# ZynqPower.net
KiCad netlist of a schematic drawn in Altium Designer
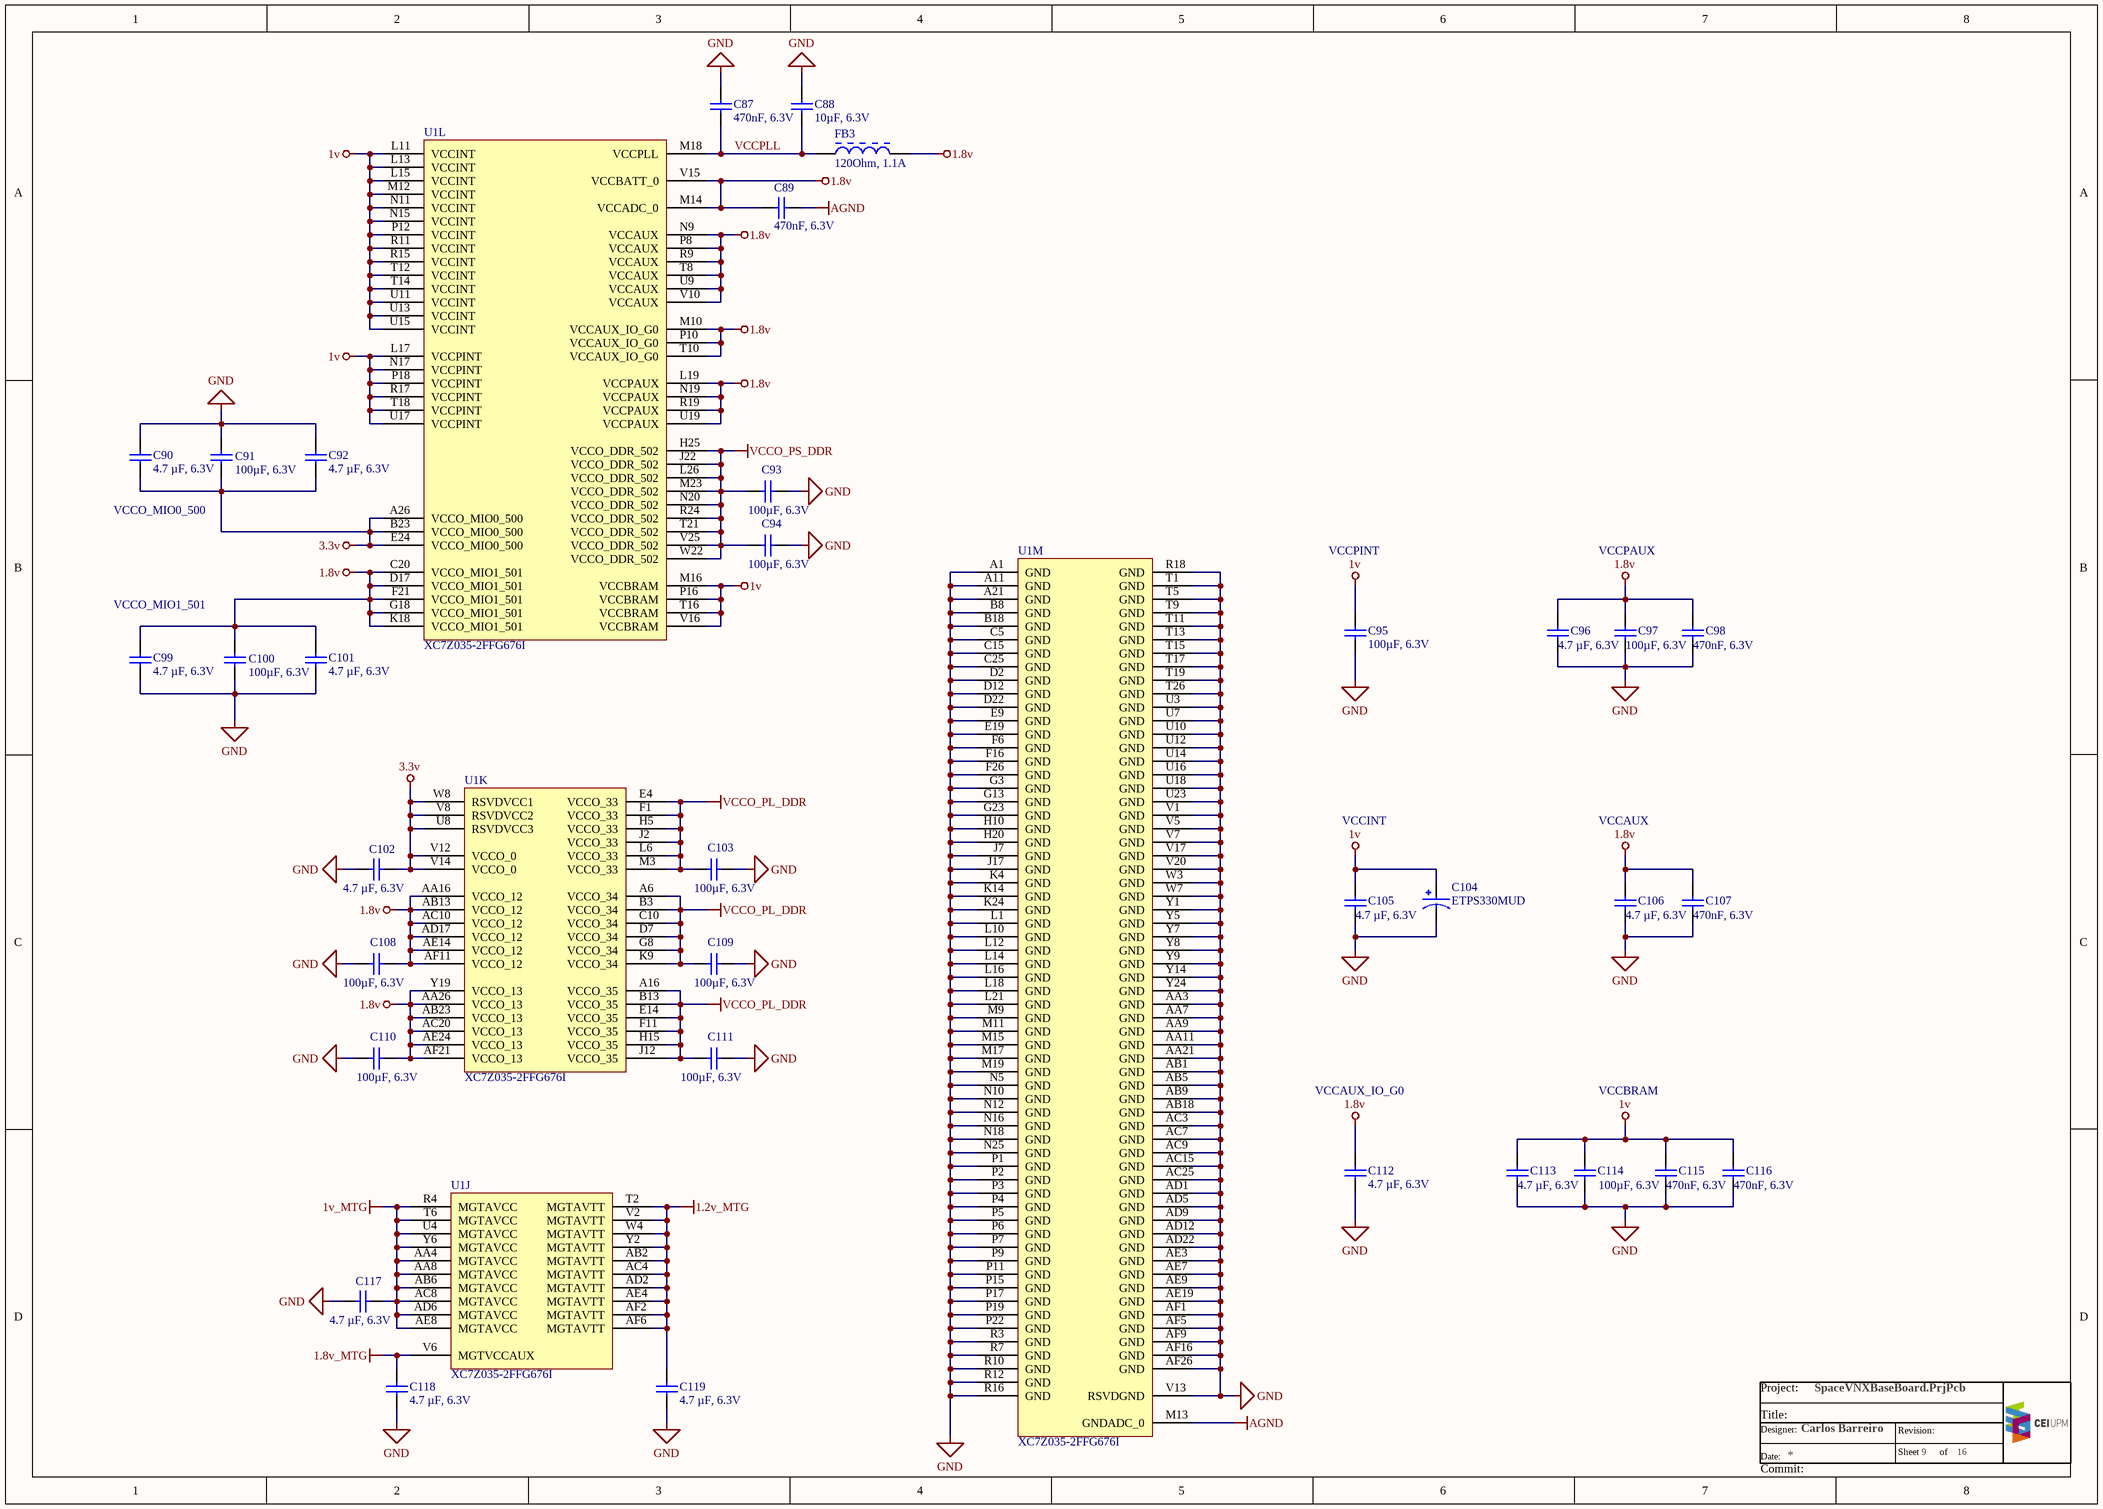
[diagram p0: ZynqPower.SchDoc]

(export (version "E")
  (design (tool "Eeschema 10.0.6"))
  (components
    (comp (ref "C87")
      (value "470nF, 6.3V")
      (footprint "WURTH_WCAP-CSGP_0402")
      (description "WCAP-CSGP Multilayer Ceramic Chip Capacitor, General Purpose, size 0402, X5R, 470nF, 6.3V")
      (fields
        (field (name "MANUFACTURER PART NUMBER") "885012105004")
        (field (name "MANUFACTURER") "Wurth Elektronik")
      )
      (libsource (lib "SpaceVNX") (part "885012105004"))
    )
    (comp (ref "C88")
      (value "10µF, 6.3V")
      (footprint "WURTH_WCAP-CSGP_0402")
      (description "WCAP-CSGP Multilayer Ceramic Chip Capacitor, General Purpose, size 0402, X5R, 10uF, 6.3V")
      (fields
        (field (name "MANUFACTURER PART NUMBER") "885012105020")
        (field (name "MANUFACTURER") "Wurth Elektronik")
      )
      (libsource (lib "SpaceVNX") (part "885012105020"))
    )
    (comp (ref "C89")
      (value "470nF, 6.3V")
      (footprint "WURTH_WCAP-CSGP_0402")
      (description "WCAP-CSGP Multilayer Ceramic Chip Capacitor, General Purpose, size 0402, X5R, 470nF, 6.3V")
      (fields
        (field (name "MANUFACTURER PART NUMBER") "885012105004")
        (field (name "MANUFACTURER") "Wurth Elektronik")
      )
      (libsource (lib "SpaceVNX") (part "885012105004"))
    )
    (comp (ref "C90")
      (value "4.7 µF, 6.3V")
      (footprint "WURTH_WCAP-CSGP_0402")
      (description "Multilayer Ceramic Capacitors MLCC, size 0402, X5R, 4.7 µF, 6.3V")
      (fields
        (field (name "MANUFACTURER PART NUMBER") "GRM155C80J475MEAAD")
        (field (name "MANUFACTURER") "Murata")
      )
      (libsource (lib "SpaceVNX") (part "GRM155C80J475MEAAD"))
    )
    (comp (ref "C91")
      (value "100µF, 6.3V")
      (footprint "WURTH_WCAP-CSGP_1206_H=1.6mm")
      (description "WCAP-CSGP Multilayer Ceramic Chip Capacitor, General Purpose, size 1206, X5R, 100uF, 6.3V")
      (fields
        (field (name "MANUFACTURER PART NUMBER") "885012108005")
        (field (name "MANUFACTURER") "Wurth Elektronik")
      )
      (libsource (lib "SpaceVNX") (part "885012108005"))
    )
    (comp (ref "C92")
      (value "4.7 µF, 6.3V")
      (footprint "WURTH_WCAP-CSGP_0402")
      (description "Multilayer Ceramic Capacitors MLCC, size 0402, X5R, 4.7 µF, 6.3V")
      (fields
        (field (name "MANUFACTURER PART NUMBER") "GRM155C80J475MEAAD")
        (field (name "MANUFACTURER") "Murata")
      )
      (libsource (lib "SpaceVNX") (part "GRM155C80J475MEAAD"))
    )
    (comp (ref "C93")
      (value "100µF, 6.3V")
      (footprint "WURTH_WCAP-CSGP_1206_H=1.6mm")
      (description "WCAP-CSGP Multilayer Ceramic Chip Capacitor, General Purpose, size 1206, X5R, 100uF, 6.3V")
      (fields
        (field (name "MANUFACTURER PART NUMBER") "885012108005")
        (field (name "MANUFACTURER") "Wurth Elektronik")
      )
      (libsource (lib "SpaceVNX") (part "885012108005"))
    )
    (comp (ref "C94")
      (value "100µF, 6.3V")
      (footprint "WURTH_WCAP-CSGP_1206_H=1.6mm")
      (description "WCAP-CSGP Multilayer Ceramic Chip Capacitor, General Purpose, size 1206, X5R, 100uF, 6.3V")
      (fields
        (field (name "MANUFACTURER PART NUMBER") "885012108005")
        (field (name "MANUFACTURER") "Wurth Elektronik")
      )
      (libsource (lib "SpaceVNX") (part "885012108005"))
    )
    (comp (ref "C95")
      (value "100µF, 6.3V")
      (footprint "WURTH_WCAP-CSGP_1206_H=1.6mm")
      (description "WCAP-CSGP Multilayer Ceramic Chip Capacitor, General Purpose, size 1206, X5R, 100uF, 6.3V")
      (fields
        (field (name "MANUFACTURER PART NUMBER") "885012108005")
        (field (name "MANUFACTURER") "Wurth Elektronik")
      )
      (libsource (lib "SpaceVNX") (part "885012108005"))
    )
    (comp (ref "C96")
      (value "4.7 µF, 6.3V")
      (footprint "WURTH_WCAP-CSGP_0402")
      (description "Multilayer Ceramic Capacitors MLCC, size 0402, X5R, 4.7 µF, 6.3V")
      (fields
        (field (name "MANUFACTURER PART NUMBER") "GRM155C80J475MEAAD")
        (field (name "MANUFACTURER") "Murata")
      )
      (libsource (lib "SpaceVNX") (part "GRM155C80J475MEAAD"))
    )
    (comp (ref "C97")
      (value "100µF, 6.3V")
      (footprint "WURTH_WCAP-CSGP_1206_H=1.6mm")
      (description "WCAP-CSGP Multilayer Ceramic Chip Capacitor, General Purpose, size 1206, X5R, 100uF, 6.3V")
      (fields
        (field (name "MANUFACTURER PART NUMBER") "885012108005")
        (field (name "MANUFACTURER") "Wurth Elektronik")
      )
      (libsource (lib "SpaceVNX") (part "885012108005"))
    )
    (comp (ref "C98")
      (value "470nF, 6.3V")
      (footprint "WURTH_WCAP-CSGP_0402")
      (description "WCAP-CSGP Multilayer Ceramic Chip Capacitor, General Purpose, size 0402, X5R, 470nF, 6.3V")
      (fields
        (field (name "MANUFACTURER PART NUMBER") "885012105004")
        (field (name "MANUFACTURER") "Wurth Elektronik")
      )
      (libsource (lib "SpaceVNX") (part "885012105004"))
    )
    (comp (ref "C99")
      (value "4.7 µF, 6.3V")
      (footprint "WURTH_WCAP-CSGP_0402")
      (description "Multilayer Ceramic Capacitors MLCC, size 0402, X5R, 4.7 µF, 6.3V")
      (fields
        (field (name "MANUFACTURER PART NUMBER") "GRM155C80J475MEAAD")
        (field (name "MANUFACTURER") "Murata")
      )
      (libsource (lib "SpaceVNX") (part "GRM155C80J475MEAAD"))
    )
    (comp (ref "C100")
      (value "100µF, 6.3V")
      (footprint "WURTH_WCAP-CSGP_1206_H=1.6mm")
      (description "WCAP-CSGP Multilayer Ceramic Chip Capacitor, General Purpose, size 1206, X5R, 100uF, 6.3V")
      (fields
        (field (name "MANUFACTURER PART NUMBER") "885012108005")
        (field (name "MANUFACTURER") "Wurth Elektronik")
      )
      (libsource (lib "SpaceVNX") (part "885012108005"))
    )
    (comp (ref "C101")
      (value "4.7 µF, 6.3V")
      (footprint "WURTH_WCAP-CSGP_0402")
      (description "Multilayer Ceramic Capacitors MLCC, size 0402, X5R, 4.7 µF, 6.3V")
      (fields
        (field (name "MANUFACTURER PART NUMBER") "GRM155C80J475MEAAD")
        (field (name "MANUFACTURER") "Murata")
      )
      (libsource (lib "SpaceVNX") (part "GRM155C80J475MEAAD"))
    )
    (comp (ref "C102")
      (value "4.7 µF, 6.3V")
      (footprint "WURTH_WCAP-CSGP_0402")
      (description "Multilayer Ceramic Capacitors MLCC, size 0402, X5R, 4.7 µF, 6.3V")
      (fields
        (field (name "MANUFACTURER PART NUMBER") "GRM155C80J475MEAAD")
        (field (name "MANUFACTURER") "Murata")
      )
      (libsource (lib "SpaceVNX") (part "GRM155C80J475MEAAD"))
    )
    (comp (ref "C103")
      (value "100µF, 6.3V")
      (footprint "WURTH_WCAP-CSGP_1206_H=1.6mm")
      (description "WCAP-CSGP Multilayer Ceramic Chip Capacitor, General Purpose, size 1206, X5R, 100uF, 6.3V")
      (fields
        (field (name "MANUFACTURER PART NUMBER") "885012108005")
        (field (name "MANUFACTURER") "Wurth Elektronik")
      )
      (libsource (lib "SpaceVNX") (part "885012108005"))
    )
    (comp (ref "C104")
      (value "ETPS330MUD")
      (footprint "PANASONIC_B1S")
      (description "Conductive Polymer Tantalum Solid Capacitors")
      (fields (field (name "MF") "Panasonic"))
      (libsource (lib "SpaceVNX") (part "ETPS330MUD"))
    )
    (comp (ref "C105")
      (value "4.7 µF, 6.3V")
      (footprint "WURTH_WCAP-CSGP_0402")
      (description "Multilayer Ceramic Capacitors MLCC, size 0402, X5R, 4.7 µF, 6.3V")
      (fields
        (field (name "MANUFACTURER PART NUMBER") "GRM155C80J475MEAAD")
        (field (name "MANUFACTURER") "Murata")
      )
      (libsource (lib "SpaceVNX") (part "GRM155C80J475MEAAD"))
    )
    (comp (ref "C106")
      (value "4.7 µF, 6.3V")
      (footprint "WURTH_WCAP-CSGP_0402")
      (description "Multilayer Ceramic Capacitors MLCC, size 0402, X5R, 4.7 µF, 6.3V")
      (fields
        (field (name "MANUFACTURER PART NUMBER") "GRM155C80J475MEAAD")
        (field (name "MANUFACTURER") "Murata")
      )
      (libsource (lib "SpaceVNX") (part "GRM155C80J475MEAAD"))
    )
    (comp (ref "C107")
      (value "470nF, 6.3V")
      (footprint "WURTH_WCAP-CSGP_0402")
      (description "WCAP-CSGP Multilayer Ceramic Chip Capacitor, General Purpose, size 0402, X5R, 470nF, 6.3V")
      (fields
        (field (name "MANUFACTURER PART NUMBER") "885012105004")
        (field (name "MANUFACTURER") "Wurth Elektronik")
      )
      (libsource (lib "SpaceVNX") (part "885012105004"))
    )
    (comp (ref "C108")
      (value "100µF, 6.3V")
      (footprint "WURTH_WCAP-CSGP_1206_H=1.6mm")
      (description "WCAP-CSGP Multilayer Ceramic Chip Capacitor, General Purpose, size 1206, X5R, 100uF, 6.3V")
      (fields
        (field (name "MANUFACTURER PART NUMBER") "885012108005")
        (field (name "MANUFACTURER") "Wurth Elektronik")
      )
      (libsource (lib "SpaceVNX") (part "885012108005"))
    )
    (comp (ref "C109")
      (value "100µF, 6.3V")
      (footprint "WURTH_WCAP-CSGP_1206_H=1.6mm")
      (description "WCAP-CSGP Multilayer Ceramic Chip Capacitor, General Purpose, size 1206, X5R, 100uF, 6.3V")
      (fields
        (field (name "MANUFACTURER PART NUMBER") "885012108005")
        (field (name "MANUFACTURER") "Wurth Elektronik")
      )
      (libsource (lib "SpaceVNX") (part "885012108005"))
    )
    (comp (ref "C110")
      (value "100µF, 6.3V")
      (footprint "WURTH_WCAP-CSGP_1206_H=1.6mm")
      (description "WCAP-CSGP Multilayer Ceramic Chip Capacitor, General Purpose, size 1206, X5R, 100uF, 6.3V")
      (fields
        (field (name "MANUFACTURER PART NUMBER") "885012108005")
        (field (name "MANUFACTURER") "Wurth Elektronik")
      )
      (libsource (lib "SpaceVNX") (part "885012108005"))
    )
    (comp (ref "C111")
      (value "100µF, 6.3V")
      (footprint "WURTH_WCAP-CSGP_1206_H=1.6mm")
      (description "WCAP-CSGP Multilayer Ceramic Chip Capacitor, General Purpose, size 1206, X5R, 100uF, 6.3V")
      (fields
        (field (name "MANUFACTURER PART NUMBER") "885012108005")
        (field (name "MANUFACTURER") "Wurth Elektronik")
      )
      (libsource (lib "SpaceVNX") (part "885012108005"))
    )
    (comp (ref "C112")
      (value "4.7 µF, 6.3V")
      (footprint "WURTH_WCAP-CSGP_0402")
      (description "Multilayer Ceramic Capacitors MLCC, size 0402, X5R, 4.7 µF, 6.3V")
      (fields
        (field (name "MANUFACTURER PART NUMBER") "GRM155C80J475MEAAD")
        (field (name "MANUFACTURER") "Murata")
      )
      (libsource (lib "SpaceVNX") (part "GRM155C80J475MEAAD"))
    )
    (comp (ref "C113")
      (value "4.7 µF, 6.3V")
      (footprint "WURTH_WCAP-CSGP_0402")
      (description "Multilayer Ceramic Capacitors MLCC, size 0402, X5R, 4.7 µF, 6.3V")
      (fields
        (field (name "MANUFACTURER PART NUMBER") "GRM155C80J475MEAAD")
        (field (name "MANUFACTURER") "Murata")
      )
      (libsource (lib "SpaceVNX") (part "GRM155C80J475MEAAD"))
    )
    (comp (ref "C114")
      (value "100µF, 6.3V")
      (footprint "WURTH_WCAP-CSGP_1206_H=1.6mm")
      (description "WCAP-CSGP Multilayer Ceramic Chip Capacitor, General Purpose, size 1206, X5R, 100uF, 6.3V")
      (fields
        (field (name "MANUFACTURER PART NUMBER") "885012108005")
        (field (name "MANUFACTURER") "Wurth Elektronik")
      )
      (libsource (lib "SpaceVNX") (part "885012108005"))
    )
    (comp (ref "C115")
      (value "470nF, 6.3V")
      (footprint "WURTH_WCAP-CSGP_0402")
      (description "WCAP-CSGP Multilayer Ceramic Chip Capacitor, General Purpose, size 0402, X5R, 470nF, 6.3V")
      (fields
        (field (name "MANUFACTURER PART NUMBER") "885012105004")
        (field (name "MANUFACTURER") "Wurth Elektronik")
      )
      (libsource (lib "SpaceVNX") (part "885012105004"))
    )
    (comp (ref "C116")
      (value "470nF, 6.3V")
      (footprint "WURTH_WCAP-CSGP_0402")
      (description "WCAP-CSGP Multilayer Ceramic Chip Capacitor, General Purpose, size 0402, X5R, 470nF, 6.3V")
      (fields
        (field (name "MANUFACTURER PART NUMBER") "885012105004")
        (field (name "MANUFACTURER") "Wurth Elektronik")
      )
      (libsource (lib "SpaceVNX") (part "885012105004"))
    )
    (comp (ref "C117")
      (value "4.7 µF, 6.3V")
      (footprint "WURTH_WCAP-CSGP_0402")
      (description "Multilayer Ceramic Capacitors MLCC, size 0402, X5R, 4.7 µF, 6.3V")
      (fields
        (field (name "MANUFACTURER PART NUMBER") "GRM155C80J475MEAAD")
        (field (name "MANUFACTURER") "Murata")
      )
      (libsource (lib "SpaceVNX") (part "GRM155C80J475MEAAD"))
    )
    (comp (ref "C118")
      (value "4.7 µF, 6.3V")
      (footprint "WURTH_WCAP-CSGP_0402")
      (description "Multilayer Ceramic Capacitors MLCC, size 0402, X5R, 4.7 µF, 6.3V")
      (fields
        (field (name "MANUFACTURER PART NUMBER") "GRM155C80J475MEAAD")
        (field (name "MANUFACTURER") "Murata")
      )
      (libsource (lib "SpaceVNX") (part "GRM155C80J475MEAAD"))
    )
    (comp (ref "C119")
      (value "4.7 µF, 6.3V")
      (footprint "WURTH_WCAP-CSGP_0402")
      (description "Multilayer Ceramic Capacitors MLCC, size 0402, X5R, 4.7 µF, 6.3V")
      (fields
        (field (name "MANUFACTURER PART NUMBER") "GRM155C80J475MEAAD")
        (field (name "MANUFACTURER") "Murata")
      )
      (libsource (lib "SpaceVNX") (part "GRM155C80J475MEAAD"))
    )
    (comp (ref "FB3")
      (value "120Ohm, 1.1A")
      (footprint "WURTH-CBF_0402")
      (description "WE-CBF SMT EMI Suppression Ferrite Bead, size 0402, 120Ohm, 1.1A")
      (fields
        (field (name "MANUFACTURER PART NUMBER") "74279271")
        (field (name "MANUFACTURER") "Wurth Elektronik")
      )
      (libsource (lib "SpaceVNX") (part "74279271"))
    )
    (comp (ref "U1")
      (value "XC7Z035-2FFG676I")
      (footprint "XILINX_FBG676")
      (fields (field (name "PARTNUMBER") "XC7Z035-2FBG676I") (field (name "GENERIC PART NUMBER") "XC7Z035"))
      (libsource (lib "SpaceVNX") (part "XC7Z035-2FFG676I"))
    )
  )
  (nets
    (net (code "1") (name "/VCCPLL") (class "Default")
      (node (ref "C87") (pin "1") (pinfunction "1_1") (pintype "passive"))
      (node (ref "C88") (pin "1") (pinfunction "1_1") (pintype "passive"))
      (node (ref "FB3") (pin "1") (pinfunction "1_1") (pintype "passive"))
      (node (ref "U1") (pin "M18") (pinfunction "VCCPLL_M18") (pintype "power_in"))
    )
    (net (code "2") (name "1.2v_MTG") (class "Default")
      (node (ref "C119") (pin "2") (pinfunction "2_2") (pintype "passive"))
      (node (ref "U1") (pin "AB2") (pinfunction "MGTAVTT_AB2") (pintype "power_in"))
      (node (ref "U1") (pin "AC4") (pinfunction "MGTAVTT_AC4") (pintype "power_in"))
      (node (ref "U1") (pin "AD2") (pinfunction "MGTAVTT_AD2") (pintype "power_in"))
      (node (ref "U1") (pin "AE4") (pinfunction "MGTAVTT_AE4") (pintype "power_in"))
      (node (ref "U1") (pin "AF2") (pinfunction "MGTAVTT_AF2") (pintype "power_in"))
      (node (ref "U1") (pin "AF6") (pinfunction "MGTAVTT_AF6") (pintype "power_in"))
      (node (ref "U1") (pin "T2") (pinfunction "MGTAVTT_T2") (pintype "power_in"))
      (node (ref "U1") (pin "V2") (pinfunction "MGTAVTT_V2") (pintype "power_in"))
      (node (ref "U1") (pin "W4") (pinfunction "MGTAVTT_W4") (pintype "power_in"))
      (node (ref "U1") (pin "Y2") (pinfunction "MGTAVTT_Y2") (pintype "power_in"))
    )
    (net (code "3") (name "1.8v") (class "Default")
      (node (ref "C100") (pin "1") (pinfunction "1_1") (pintype "passive"))
      (node (ref "C101") (pin "2") (pinfunction "2_2") (pintype "passive"))
      (node (ref "C106") (pin "2") (pinfunction "2_2") (pintype "passive"))
      (node (ref "C107") (pin "2") (pinfunction "2_2") (pintype "passive"))
      (node (ref "C108") (pin "1") (pinfunction "1_1") (pintype "passive"))
      (node (ref "C110") (pin "1") (pinfunction "1_1") (pintype "passive"))
      (node (ref "C112") (pin "2") (pinfunction "2_2") (pintype "passive"))
      (node (ref "C89") (pin "2") (pinfunction "2_2") (pintype "passive"))
      (node (ref "C96") (pin "1") (pinfunction "1_1") (pintype "passive"))
      (node (ref "C97") (pin "2") (pinfunction "2_2") (pintype "passive"))
      (node (ref "C98") (pin "2") (pinfunction "2_2") (pintype "passive"))
      (node (ref "C99") (pin "2") (pinfunction "2_2") (pintype "passive"))
      (node (ref "FB3") (pin "2") (pinfunction "2_2") (pintype "passive"))
      (node (ref "U1") (pin "AA16") (pinfunction "VCCO_12_AA16") (pintype "power_in"))
      (node (ref "U1") (pin "AA26") (pinfunction "VCCO_13_AA26") (pintype "power_in"))
      (node (ref "U1") (pin "AB13") (pinfunction "VCCO_12_AB13") (pintype "power_in"))
      (node (ref "U1") (pin "AB23") (pinfunction "VCCO_13_AB23") (pintype "power_in"))
      (node (ref "U1") (pin "AC10") (pinfunction "VCCO_12_AC10") (pintype "power_in"))
      (node (ref "U1") (pin "AC20") (pinfunction "VCCO_13_AC20") (pintype "power_in"))
      (node (ref "U1") (pin "AD17") (pinfunction "VCCO_12_AD17") (pintype "power_in"))
      (node (ref "U1") (pin "AE14") (pinfunction "VCCO_12_AE14") (pintype "power_in"))
      (node (ref "U1") (pin "AE24") (pinfunction "VCCO_13_AE24") (pintype "power_in"))
      (node (ref "U1") (pin "AF11") (pinfunction "VCCO_12_AF11") (pintype "power_in"))
      (node (ref "U1") (pin "AF21") (pinfunction "VCCO_13_AF21") (pintype "power_in"))
      (node (ref "U1") (pin "C20") (pinfunction "VCCO_MIO1_501_C20") (pintype "power_in"))
      (node (ref "U1") (pin "D17") (pinfunction "VCCO_MIO1_501_D17") (pintype "power_in"))
      (node (ref "U1") (pin "F21") (pinfunction "VCCO_MIO1_501_F21") (pintype "power_in"))
      (node (ref "U1") (pin "G18") (pinfunction "VCCO_MIO1_501_G18") (pintype "power_in"))
      (node (ref "U1") (pin "K18") (pinfunction "VCCO_MIO1_501_K18") (pintype "power_in"))
      (node (ref "U1") (pin "L19") (pinfunction "VCCPAUX_L19") (pintype "power_in"))
      (node (ref "U1") (pin "M10") (pinfunction "VCCAUX_IO_G0_M10") (pintype "power_in"))
      (node (ref "U1") (pin "M14") (pinfunction "VCCADC_0_M14") (pintype "power_in"))
      (node (ref "U1") (pin "N19") (pinfunction "VCCPAUX_N19") (pintype "power_in"))
      (node (ref "U1") (pin "N9") (pinfunction "VCCAUX_N9") (pintype "power_in"))
      (node (ref "U1") (pin "P10") (pinfunction "VCCAUX_IO_G0_P10") (pintype "power_in"))
      (node (ref "U1") (pin "P8") (pinfunction "VCCAUX_P8") (pintype "power_in"))
      (node (ref "U1") (pin "R19") (pinfunction "VCCPAUX_R19") (pintype "power_in"))
      (node (ref "U1") (pin "R9") (pinfunction "VCCAUX_R9") (pintype "power_in"))
      (node (ref "U1") (pin "T10") (pinfunction "VCCAUX_IO_G0_T10") (pintype "power_in"))
      (node (ref "U1") (pin "T8") (pinfunction "VCCAUX_T8") (pintype "power_in"))
      (node (ref "U1") (pin "U19") (pinfunction "VCCPAUX_U19") (pintype "power_in"))
      (node (ref "U1") (pin "U9") (pinfunction "VCCAUX_U9") (pintype "power_in"))
      (node (ref "U1") (pin "V10") (pinfunction "VCCAUX_V10") (pintype "power_in"))
      (node (ref "U1") (pin "V15") (pinfunction "VCCBATT_0_V15") (pintype "power_in"))
      (node (ref "U1") (pin "Y19") (pinfunction "VCCO_13_Y19") (pintype "power_in"))
    )
    (net (code "4") (name "1.8v_MTG") (class "Default")
      (node (ref "C118") (pin "2") (pinfunction "2_2") (pintype "passive"))
      (node (ref "U1") (pin "V6") (pinfunction "MGTVCCAUX_V6") (pintype "power_in"))
    )
    (net (code "5") (name "1v") (class "Default")
      (node (ref "C104") (pin "1") (pinfunction "1_1") (pintype "passive"))
      (node (ref "C105") (pin "1") (pinfunction "1_1") (pintype "passive"))
      (node (ref "C113") (pin "1") (pinfunction "1_1") (pintype "passive"))
      (node (ref "C114") (pin "2") (pinfunction "2_2") (pintype "passive"))
      (node (ref "C115") (pin "2") (pinfunction "2_2") (pintype "passive"))
      (node (ref "C116") (pin "2") (pinfunction "2_2") (pintype "passive"))
      (node (ref "C95") (pin "2") (pinfunction "2_2") (pintype "passive"))
      (node (ref "U1") (pin "L11") (pinfunction "VCCINT_L11") (pintype "power_in"))
      (node (ref "U1") (pin "L13") (pinfunction "VCCINT_L13") (pintype "power_in"))
      (node (ref "U1") (pin "L15") (pinfunction "VCCINT_L15") (pintype "power_in"))
      (node (ref "U1") (pin "L17") (pinfunction "VCCPINT_L17") (pintype "power_in"))
      (node (ref "U1") (pin "M12") (pinfunction "VCCINT_M12") (pintype "power_in"))
      (node (ref "U1") (pin "M16") (pinfunction "VCCBRAM_M16") (pintype "power_in"))
      (node (ref "U1") (pin "N11") (pinfunction "VCCINT_N11") (pintype "power_in"))
      (node (ref "U1") (pin "N15") (pinfunction "VCCINT_N15") (pintype "power_in"))
      (node (ref "U1") (pin "N17") (pinfunction "VCCPINT_N17") (pintype "power_in"))
      (node (ref "U1") (pin "P12") (pinfunction "VCCINT_P12") (pintype "power_in"))
      (node (ref "U1") (pin "P16") (pinfunction "VCCBRAM_P16") (pintype "power_in"))
      (node (ref "U1") (pin "P18") (pinfunction "VCCPINT_P18") (pintype "power_in"))
      (node (ref "U1") (pin "R11") (pinfunction "VCCINT_R11") (pintype "power_in"))
      (node (ref "U1") (pin "R15") (pinfunction "VCCINT_R15") (pintype "power_in"))
      (node (ref "U1") (pin "R17") (pinfunction "VCCPINT_R17") (pintype "power_in"))
      (node (ref "U1") (pin "T12") (pinfunction "VCCINT_T12") (pintype "power_in"))
      (node (ref "U1") (pin "T14") (pinfunction "VCCINT_T14") (pintype "power_in"))
      (node (ref "U1") (pin "T16") (pinfunction "VCCBRAM_T16") (pintype "power_in"))
      (node (ref "U1") (pin "T18") (pinfunction "VCCPINT_T18") (pintype "power_in"))
      (node (ref "U1") (pin "U11") (pinfunction "VCCINT_U11") (pintype "power_in"))
      (node (ref "U1") (pin "U13") (pinfunction "VCCINT_U13") (pintype "power_in"))
      (node (ref "U1") (pin "U15") (pinfunction "VCCINT_U15") (pintype "power_in"))
      (node (ref "U1") (pin "U17") (pinfunction "VCCPINT_U17") (pintype "power_in"))
      (node (ref "U1") (pin "V16") (pinfunction "VCCBRAM_V16") (pintype "power_in"))
    )
    (net (code "6") (name "1v_MTG") (class "Default")
      (node (ref "C117") (pin "2") (pinfunction "2_2") (pintype "passive"))
      (node (ref "U1") (pin "AA4") (pinfunction "MGTAVCC_AA4") (pintype "power_in"))
      (node (ref "U1") (pin "AA8") (pinfunction "MGTAVCC_AA8") (pintype "power_in"))
      (node (ref "U1") (pin "AB6") (pinfunction "MGTAVCC_AB6") (pintype "power_in"))
      (node (ref "U1") (pin "AC8") (pinfunction "MGTAVCC_AC8") (pintype "power_in"))
      (node (ref "U1") (pin "AD6") (pinfunction "MGTAVCC_AD6") (pintype "power_in"))
      (node (ref "U1") (pin "AE8") (pinfunction "MGTAVCC_AE8") (pintype "power_in"))
      (node (ref "U1") (pin "R4") (pinfunction "MGTAVCC_R4") (pintype "power_in"))
      (node (ref "U1") (pin "T6") (pinfunction "MGTAVCC_T6") (pintype "power_in"))
      (node (ref "U1") (pin "U4") (pinfunction "MGTAVCC_U4") (pintype "power_in"))
      (node (ref "U1") (pin "Y6") (pinfunction "MGTAVCC_Y6") (pintype "power_in"))
    )
    (net (code "7") (name "3.3v") (class "Default")
      (node (ref "C102") (pin "2") (pinfunction "2_2") (pintype "passive"))
      (node (ref "C90") (pin "2") (pinfunction "2_2") (pintype "passive"))
      (node (ref "C91") (pin "1") (pinfunction "1_1") (pintype "passive"))
      (node (ref "C92") (pin "2") (pinfunction "2_2") (pintype "passive"))
      (node (ref "U1") (pin "A26") (pinfunction "VCCO_MIO0_500_A26") (pintype "power_in"))
      (node (ref "U1") (pin "B23") (pinfunction "VCCO_MIO0_500_B23") (pintype "power_in"))
      (node (ref "U1") (pin "E24") (pinfunction "VCCO_MIO0_500_E24") (pintype "power_in"))
      (node (ref "U1") (pin "U8") (pinfunction "RSVDVCC3_U8") (pintype "power_in"))
      (node (ref "U1") (pin "V12") (pinfunction "VCCO_0_V12") (pintype "power_in"))
      (node (ref "U1") (pin "V14") (pinfunction "VCCO_0_V14") (pintype "power_in"))
      (node (ref "U1") (pin "V8") (pinfunction "RSVDVCC2_V8") (pintype "power_in"))
      (node (ref "U1") (pin "W8") (pinfunction "RSVDVCC1_W8") (pintype "power_in"))
    )
    (net (code "8") (name "AGND") (class "Default")
      (node (ref "C89") (pin "1") (pinfunction "1_1") (pintype "passive"))
      (node (ref "U1") (pin "M13") (pinfunction "GNDADC_0_M13") (pintype "power_in"))
    )
    (net (code "9") (name "GND") (class "Default")
      (node (ref "C100") (pin "2") (pinfunction "2_2") (pintype "passive"))
      (node (ref "C101") (pin "1") (pinfunction "1_1") (pintype "passive"))
      (node (ref "C102") (pin "1") (pinfunction "1_1") (pintype "passive"))
      (node (ref "C103") (pin "2") (pinfunction "2_2") (pintype "passive"))
      (node (ref "C104") (pin "2") (pinfunction "2_2") (pintype "passive"))
      (node (ref "C105") (pin "2") (pinfunction "2_2") (pintype "passive"))
      (node (ref "C106") (pin "1") (pinfunction "1_1") (pintype "passive"))
      (node (ref "C107") (pin "1") (pinfunction "1_1") (pintype "passive"))
      (node (ref "C108") (pin "2") (pinfunction "2_2") (pintype "passive"))
      (node (ref "C109") (pin "2") (pinfunction "2_2") (pintype "passive"))
      (node (ref "C110") (pin "2") (pinfunction "2_2") (pintype "passive"))
      (node (ref "C111") (pin "2") (pinfunction "2_2") (pintype "passive"))
      (node (ref "C112") (pin "1") (pinfunction "1_1") (pintype "passive"))
      (node (ref "C113") (pin "2") (pinfunction "2_2") (pintype "passive"))
      (node (ref "C114") (pin "1") (pinfunction "1_1") (pintype "passive"))
      (node (ref "C115") (pin "1") (pinfunction "1_1") (pintype "passive"))
      (node (ref "C116") (pin "1") (pinfunction "1_1") (pintype "passive"))
      (node (ref "C117") (pin "1") (pinfunction "1_1") (pintype "passive"))
      (node (ref "C118") (pin "1") (pinfunction "1_1") (pintype "passive"))
      (node (ref "C119") (pin "1") (pinfunction "1_1") (pintype "passive"))
      (node (ref "C87") (pin "2") (pinfunction "2_2") (pintype "passive"))
      (node (ref "C88") (pin "2") (pinfunction "2_2") (pintype "passive"))
      (node (ref "C90") (pin "1") (pinfunction "1_1") (pintype "passive"))
      (node (ref "C91") (pin "2") (pinfunction "2_2") (pintype "passive"))
      (node (ref "C92") (pin "1") (pinfunction "1_1") (pintype "passive"))
      (node (ref "C93") (pin "2") (pinfunction "2_2") (pintype "passive"))
      (node (ref "C94") (pin "2") (pinfunction "2_2") (pintype "passive"))
      (node (ref "C95") (pin "1") (pinfunction "1_1") (pintype "passive"))
      (node (ref "C96") (pin "2") (pinfunction "2_2") (pintype "passive"))
      (node (ref "C97") (pin "1") (pinfunction "1_1") (pintype "passive"))
      (node (ref "C98") (pin "1") (pinfunction "1_1") (pintype "passive"))
      (node (ref "C99") (pin "1") (pinfunction "1_1") (pintype "passive"))
      (node (ref "U1") (pin "A1") (pinfunction "GND_A1") (pintype "power_in"))
      (node (ref "U1") (pin "A11") (pinfunction "GND_A11") (pintype "power_in"))
      (node (ref "U1") (pin "A21") (pinfunction "GND_A21") (pintype "power_in"))
      (node (ref "U1") (pin "AA11") (pinfunction "GND_AA11") (pintype "power_in"))
      (node (ref "U1") (pin "AA21") (pinfunction "GND_AA21") (pintype "power_in"))
      (node (ref "U1") (pin "AA3") (pinfunction "GND_AA3") (pintype "power_in"))
      (node (ref "U1") (pin "AA7") (pinfunction "GND_AA7") (pintype "power_in"))
      (node (ref "U1") (pin "AA9") (pinfunction "GND_AA9") (pintype "power_in"))
      (node (ref "U1") (pin "AB1") (pinfunction "GND_AB1") (pintype "power_in"))
      (node (ref "U1") (pin "AB18") (pinfunction "GND_AB18") (pintype "power_in"))
      (node (ref "U1") (pin "AB5") (pinfunction "GND_AB5") (pintype "power_in"))
      (node (ref "U1") (pin "AB9") (pinfunction "GND_AB9") (pintype "power_in"))
      (node (ref "U1") (pin "AC15") (pinfunction "GND_AC15") (pintype "power_in"))
      (node (ref "U1") (pin "AC25") (pinfunction "GND_AC25") (pintype "power_in"))
      (node (ref "U1") (pin "AC3") (pinfunction "GND_AC3") (pintype "power_in"))
      (node (ref "U1") (pin "AC7") (pinfunction "GND_AC7") (pintype "power_in"))
      (node (ref "U1") (pin "AC9") (pinfunction "GND_AC9") (pintype "power_in"))
      (node (ref "U1") (pin "AD1") (pinfunction "GND_AD1") (pintype "power_in"))
      (node (ref "U1") (pin "AD12") (pinfunction "GND_AD12") (pintype "power_in"))
      (node (ref "U1") (pin "AD22") (pinfunction "GND_AD22") (pintype "power_in"))
      (node (ref "U1") (pin "AD5") (pinfunction "GND_AD5") (pintype "power_in"))
      (node (ref "U1") (pin "AD9") (pinfunction "GND_AD9") (pintype "power_in"))
      (node (ref "U1") (pin "AE19") (pinfunction "GND_AE19") (pintype "power_in"))
      (node (ref "U1") (pin "AE3") (pinfunction "GND_AE3") (pintype "power_in"))
      (node (ref "U1") (pin "AE7") (pinfunction "GND_AE7") (pintype "power_in"))
      (node (ref "U1") (pin "AE9") (pinfunction "GND_AE9") (pintype "power_in"))
      (node (ref "U1") (pin "AF1") (pinfunction "GND_AF1") (pintype "power_in"))
      (node (ref "U1") (pin "AF16") (pinfunction "GND_AF16") (pintype "power_in"))
      (node (ref "U1") (pin "AF26") (pinfunction "GND_AF26") (pintype "power_in"))
      (node (ref "U1") (pin "AF5") (pinfunction "GND_AF5") (pintype "power_in"))
      (node (ref "U1") (pin "AF9") (pinfunction "GND_AF9") (pintype "power_in"))
      (node (ref "U1") (pin "B18") (pinfunction "GND_B18") (pintype "power_in"))
      (node (ref "U1") (pin "B8") (pinfunction "GND_B8") (pintype "power_in"))
      (node (ref "U1") (pin "C15") (pinfunction "GND_C15") (pintype "power_in"))
      (node (ref "U1") (pin "C25") (pinfunction "GND_C25") (pintype "power_in"))
      (node (ref "U1") (pin "C5") (pinfunction "GND_C5") (pintype "power_in"))
      (node (ref "U1") (pin "D12") (pinfunction "GND_D12") (pintype "power_in"))
      (node (ref "U1") (pin "D2") (pinfunction "GND_D2") (pintype "power_in"))
      (node (ref "U1") (pin "D22") (pinfunction "GND_D22") (pintype "power_in"))
      (node (ref "U1") (pin "E19") (pinfunction "GND_E19") (pintype "power_in"))
      (node (ref "U1") (pin "E9") (pinfunction "GND_E9") (pintype "power_in"))
      (node (ref "U1") (pin "F16") (pinfunction "GND_F16") (pintype "power_in"))
      (node (ref "U1") (pin "F26") (pinfunction "GND_F26") (pintype "power_in"))
      (node (ref "U1") (pin "F6") (pinfunction "GND_F6") (pintype "power_in"))
      (node (ref "U1") (pin "G13") (pinfunction "GND_G13") (pintype "power_in"))
      (node (ref "U1") (pin "G23") (pinfunction "GND_G23") (pintype "power_in"))
      (node (ref "U1") (pin "G3") (pinfunction "GND_G3") (pintype "power_in"))
      (node (ref "U1") (pin "H10") (pinfunction "GND_H10") (pintype "power_in"))
      (node (ref "U1") (pin "H20") (pinfunction "GND_H20") (pintype "power_in"))
      (node (ref "U1") (pin "J17") (pinfunction "GND_J17") (pintype "power_in"))
      (node (ref "U1") (pin "J7") (pinfunction "GND_J7") (pintype "power_in"))
      (node (ref "U1") (pin "K14") (pinfunction "GND_K14") (pintype "power_in"))
      (node (ref "U1") (pin "K24") (pinfunction "GND_K24") (pintype "power_in"))
      (node (ref "U1") (pin "K4") (pinfunction "GND_K4") (pintype "power_in"))
      (node (ref "U1") (pin "L1") (pinfunction "GND_L1") (pintype "power_in"))
      (node (ref "U1") (pin "L10") (pinfunction "GND_L10") (pintype "power_in"))
      (node (ref "U1") (pin "L12") (pinfunction "GND_L12") (pintype "power_in"))
      (node (ref "U1") (pin "L14") (pinfunction "GND_L14") (pintype "power_in"))
      (node (ref "U1") (pin "L16") (pinfunction "GND_L16") (pintype "power_in"))
      (node (ref "U1") (pin "L18") (pinfunction "GND_L18") (pintype "power_in"))
      (node (ref "U1") (pin "L21") (pinfunction "GND_L21") (pintype "power_in"))
      (node (ref "U1") (pin "M11") (pinfunction "GND_M11") (pintype "power_in"))
      (node (ref "U1") (pin "M15") (pinfunction "GND_M15") (pintype "power_in"))
      (node (ref "U1") (pin "M17") (pinfunction "GND_M17") (pintype "power_in"))
      (node (ref "U1") (pin "M19") (pinfunction "GND_M19") (pintype "power_in"))
      (node (ref "U1") (pin "M9") (pinfunction "GND_M9") (pintype "power_in"))
      (node (ref "U1") (pin "N10") (pinfunction "GND_N10") (pintype "power_in"))
      (node (ref "U1") (pin "N12") (pinfunction "GND_N12") (pintype "power_in"))
      (node (ref "U1") (pin "N16") (pinfunction "GND_N16") (pintype "power_in"))
      (node (ref "U1") (pin "N18") (pinfunction "GND_N18") (pintype "power_in"))
      (node (ref "U1") (pin "N25") (pinfunction "GND_N25") (pintype "power_in"))
      (node (ref "U1") (pin "N5") (pinfunction "GND_N5") (pintype "power_in"))
      (node (ref "U1") (pin "P1") (pinfunction "GND_P1") (pintype "power_in"))
      (node (ref "U1") (pin "P11") (pinfunction "GND_P11") (pintype "power_in"))
      (node (ref "U1") (pin "P15") (pinfunction "GND_P15") (pintype "power_in"))
      (node (ref "U1") (pin "P17") (pinfunction "GND_P17") (pintype "power_in"))
      (node (ref "U1") (pin "P19") (pinfunction "GND_P19") (pintype "power_in"))
      (node (ref "U1") (pin "P2") (pinfunction "GND_P2") (pintype "power_in"))
      (node (ref "U1") (pin "P22") (pinfunction "GND_P22") (pintype "power_in"))
      (node (ref "U1") (pin "P3") (pinfunction "GND_P3") (pintype "power_in"))
      (node (ref "U1") (pin "P4") (pinfunction "GND_P4") (pintype "power_in"))
      (node (ref "U1") (pin "P5") (pinfunction "GND_P5") (pintype "power_in"))
      (node (ref "U1") (pin "P6") (pinfunction "GND_P6") (pintype "power_in"))
      (node (ref "U1") (pin "P7") (pinfunction "GND_P7") (pintype "power_in"))
      (node (ref "U1") (pin "P9") (pinfunction "GND_P9") (pintype "power_in"))
      (node (ref "U1") (pin "R10") (pinfunction "GND_R10") (pintype "power_in"))
      (node (ref "U1") (pin "R12") (pinfunction "GND_R12") (pintype "power_in"))
      (node (ref "U1") (pin "R16") (pinfunction "GND_R16") (pintype "power_in"))
      (node (ref "U1") (pin "R18") (pinfunction "GND_R18") (pintype "power_in"))
      (node (ref "U1") (pin "R3") (pinfunction "GND_R3") (pintype "power_in"))
      (node (ref "U1") (pin "R7") (pinfunction "GND_R7") (pintype "power_in"))
      (node (ref "U1") (pin "T1") (pinfunction "GND_T1") (pintype "power_in"))
      (node (ref "U1") (pin "T11") (pinfunction "GND_T11") (pintype "power_in"))
      (node (ref "U1") (pin "T13") (pinfunction "GND_T13") (pintype "power_in"))
      (node (ref "U1") (pin "T15") (pinfunction "GND_T15") (pintype "power_in"))
      (node (ref "U1") (pin "T17") (pinfunction "GND_T17") (pintype "power_in"))
      (node (ref "U1") (pin "T19") (pinfunction "GND_T19") (pintype "power_in"))
      (node (ref "U1") (pin "T26") (pinfunction "GND_T26") (pintype "power_in"))
      (node (ref "U1") (pin "T5") (pinfunction "GND_T5") (pintype "power_in"))
      (node (ref "U1") (pin "T9") (pinfunction "GND_T9") (pintype "power_in"))
      (node (ref "U1") (pin "U10") (pinfunction "GND_U10") (pintype "power_in"))
      (node (ref "U1") (pin "U12") (pinfunction "GND_U12") (pintype "power_in"))
      (node (ref "U1") (pin "U14") (pinfunction "GND_U14") (pintype "power_in"))
      (node (ref "U1") (pin "U16") (pinfunction "GND_U16") (pintype "power_in"))
      (node (ref "U1") (pin "U18") (pinfunction "GND_U18") (pintype "power_in"))
      (node (ref "U1") (pin "U23") (pinfunction "GND_U23") (pintype "power_in"))
      (node (ref "U1") (pin "U3") (pinfunction "GND_U3") (pintype "power_in"))
      (node (ref "U1") (pin "U7") (pinfunction "GND_U7") (pintype "power_in"))
      (node (ref "U1") (pin "V1") (pinfunction "GND_V1") (pintype "power_in"))
      (node (ref "U1") (pin "V13") (pinfunction "RSVDGND_V13") (pintype "power_in"))
      (node (ref "U1") (pin "V17") (pinfunction "GND_V17") (pintype "power_in"))
      (node (ref "U1") (pin "V20") (pinfunction "GND_V20") (pintype "power_in"))
      (node (ref "U1") (pin "V5") (pinfunction "GND_V5") (pintype "power_in"))
      (node (ref "U1") (pin "V7") (pinfunction "GND_V7") (pintype "power_in"))
      (node (ref "U1") (pin "W3") (pinfunction "GND_W3") (pintype "power_in"))
      (node (ref "U1") (pin "W7") (pinfunction "GND_W7") (pintype "power_in"))
      (node (ref "U1") (pin "Y1") (pinfunction "GND_Y1") (pintype "power_in"))
      (node (ref "U1") (pin "Y14") (pinfunction "GND_Y14") (pintype "power_in"))
      (node (ref "U1") (pin "Y24") (pinfunction "GND_Y24") (pintype "power_in"))
      (node (ref "U1") (pin "Y5") (pinfunction "GND_Y5") (pintype "power_in"))
      (node (ref "U1") (pin "Y7") (pinfunction "GND_Y7") (pintype "power_in"))
      (node (ref "U1") (pin "Y8") (pinfunction "GND_Y8") (pintype "power_in"))
      (node (ref "U1") (pin "Y9") (pinfunction "GND_Y9") (pintype "power_in"))
    )
    (net (code "10") (name "VCCO_PL_DDR") (class "Default")
      (node (ref "C103") (pin "1") (pinfunction "1_1") (pintype "passive"))
      (node (ref "C109") (pin "1") (pinfunction "1_1") (pintype "passive"))
      (node (ref "C111") (pin "1") (pinfunction "1_1") (pintype "passive"))
      (node (ref "U1") (pin "A16") (pinfunction "VCCO_35_A16") (pintype "power_in"))
      (node (ref "U1") (pin "A6") (pinfunction "VCCO_34_A6") (pintype "power_in"))
      (node (ref "U1") (pin "B13") (pinfunction "VCCO_35_B13") (pintype "power_in"))
      (node (ref "U1") (pin "B3") (pinfunction "VCCO_34_B3") (pintype "power_in"))
      (node (ref "U1") (pin "C10") (pinfunction "VCCO_34_C10") (pintype "power_in"))
      (node (ref "U1") (pin "D7") (pinfunction "VCCO_34_D7") (pintype "power_in"))
      (node (ref "U1") (pin "E14") (pinfunction "VCCO_35_E14") (pintype "power_in"))
      (node (ref "U1") (pin "E4") (pinfunction "VCCO_33_E4") (pintype "power_in"))
      (node (ref "U1") (pin "F1") (pinfunction "VCCO_33_F1") (pintype "power_in"))
      (node (ref "U1") (pin "F11") (pinfunction "VCCO_35_F11") (pintype "power_in"))
      (node (ref "U1") (pin "G8") (pinfunction "VCCO_34_G8") (pintype "power_in"))
      (node (ref "U1") (pin "H15") (pinfunction "VCCO_35_H15") (pintype "power_in"))
      (node (ref "U1") (pin "H5") (pinfunction "VCCO_33_H5") (pintype "power_in"))
      (node (ref "U1") (pin "J12") (pinfunction "VCCO_35_J12") (pintype "power_in"))
      (node (ref "U1") (pin "J2") (pinfunction "VCCO_33_J2") (pintype "power_in"))
      (node (ref "U1") (pin "K9") (pinfunction "VCCO_34_K9") (pintype "power_in"))
      (node (ref "U1") (pin "L6") (pinfunction "VCCO_33_L6") (pintype "power_in"))
      (node (ref "U1") (pin "M3") (pinfunction "VCCO_33_M3") (pintype "power_in"))
    )
    (net (code "11") (name "VCCO_PS_DDR") (class "Default")
      (node (ref "C93") (pin "1") (pinfunction "1_1") (pintype "passive"))
      (node (ref "C94") (pin "1") (pinfunction "1_1") (pintype "passive"))
      (node (ref "U1") (pin "H25") (pinfunction "VCCO_DDR_502_H25") (pintype "power_in"))
      (node (ref "U1") (pin "J22") (pinfunction "VCCO_DDR_502_J22") (pintype "power_in"))
      (node (ref "U1") (pin "L26") (pinfunction "VCCO_DDR_502_L26") (pintype "power_in"))
      (node (ref "U1") (pin "M23") (pinfunction "VCCO_DDR_502_M23") (pintype "power_in"))
      (node (ref "U1") (pin "N20") (pinfunction "VCCO_DDR_502_N20") (pintype "power_in"))
      (node (ref "U1") (pin "R24") (pinfunction "VCCO_DDR_502_R24") (pintype "power_in"))
      (node (ref "U1") (pin "T21") (pinfunction "VCCO_DDR_502_T21") (pintype "power_in"))
      (node (ref "U1") (pin "V25") (pinfunction "VCCO_DDR_502_V25") (pintype "power_in"))
      (node (ref "U1") (pin "W22") (pinfunction "VCCO_DDR_502_W22") (pintype "power_in"))
    )
  )
)
